# 11-multimodal-combined-sensor.net
KiCad netlist of a schematic drawn in Altium Designer
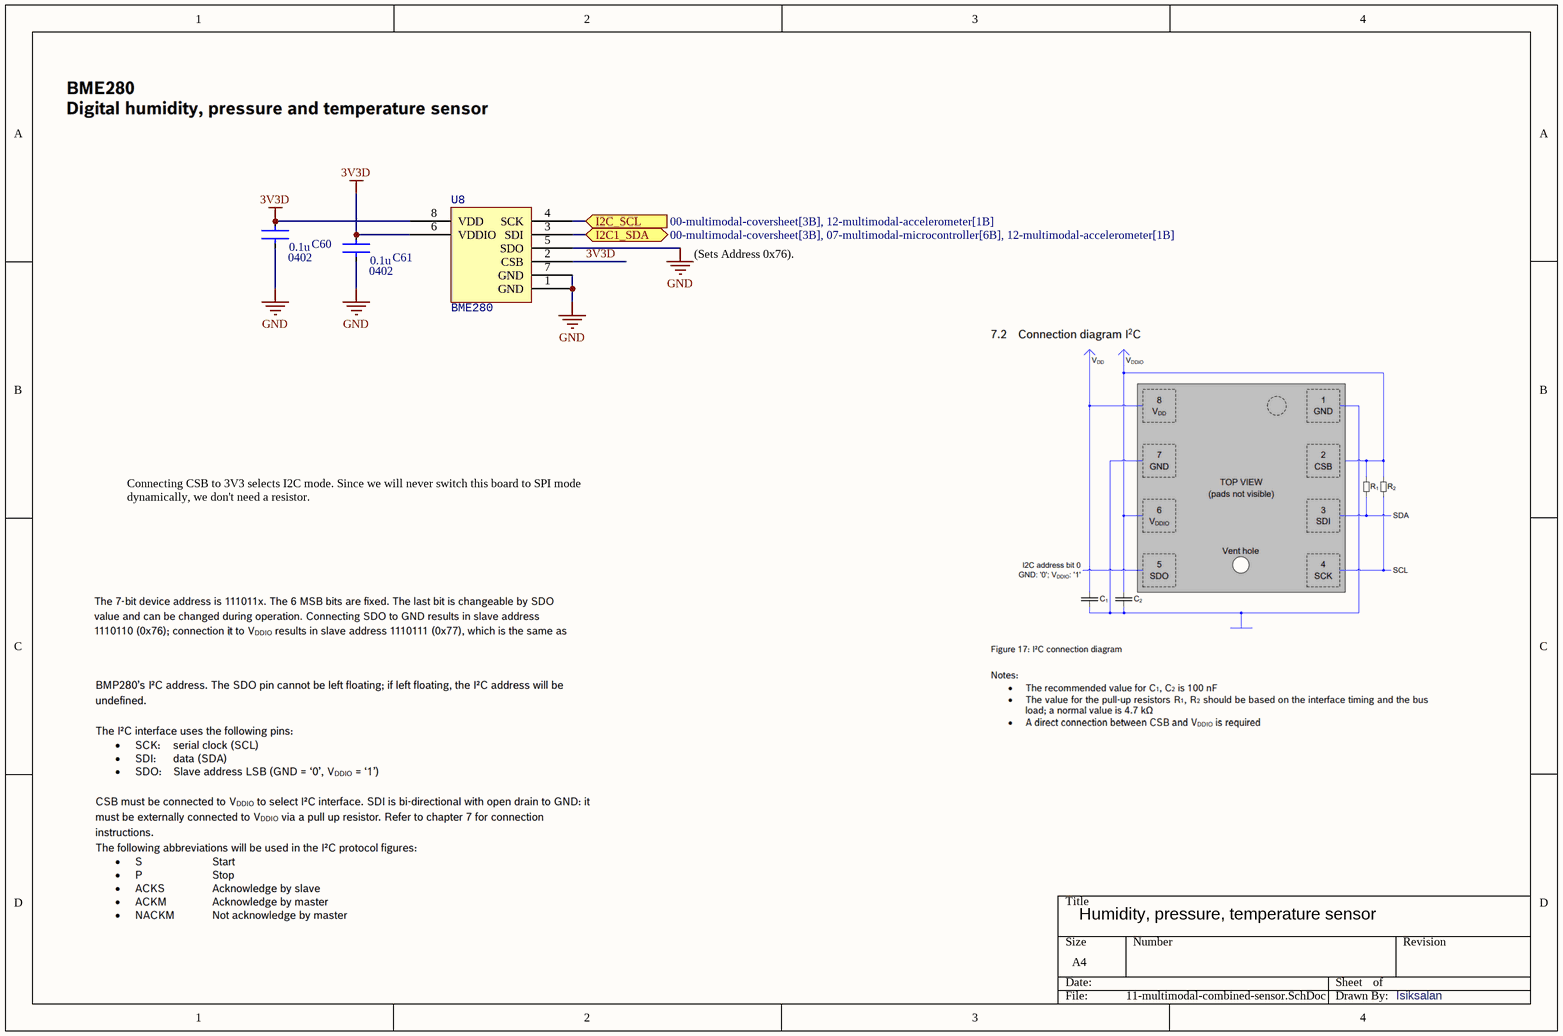
[diagram p0: 11-multimodal-combined-sensor.SchDoc]

(export (version "E")
  (design (tool "Eeschema 10.0.6"))
  (components
    (comp (ref "C60")
      (value "C1005X7R1H104K050BB")
      (footprint "CAPTDK0402")
      (description "CAP CER 0.1UF 50V X7R 0402")
      (libsource (lib "multimodal") (part "C1005X7R1H104K050BB"))
    )
    (comp (ref "C61")
      (value "C1005X7R1H104K050BB")
      (footprint "CAPTDK0402")
      (description "CAP CER 0.1UF 50V X7R 0402")
      (libsource (lib "multimodal") (part "C1005X7R1H104K050BB"))
    )
    (comp (ref "U8")
      (value "BME280")
      (footprint "BME280_FOOTPRINT")
      (libsource (lib "multimodal") (part "BME280"))
    )
  )
  (nets
    (net (code "1") (name "/I2C1_SDA") (class "Default")
      (node (ref "U8") (pin "3") (pinfunction "SDI_3") (pintype "passive"))
    )
    (net (code "2") (name "/I2C_SCL") (class "Default")
      (node (ref "U8") (pin "4") (pinfunction "SCK_4") (pintype "passive"))
    )
    (net (code "3") (name "3V3D") (class "Default")
      (node (ref "C60") (pin "1") (pinfunction "1_1") (pintype "passive"))
      (node (ref "C61") (pin "1") (pinfunction "1_1") (pintype "passive"))
      (node (ref "U8") (pin "2") (pinfunction "CSB_2") (pintype "passive"))
      (node (ref "U8") (pin "6") (pinfunction "VDDIO_6") (pintype "passive"))
      (node (ref "U8") (pin "8") (pinfunction "VDD_8") (pintype "passive"))
    )
    (net (code "4") (name "GND") (class "Default")
      (node (ref "C60") (pin "2") (pinfunction "2_2") (pintype "passive"))
      (node (ref "C61") (pin "2") (pinfunction "2_2") (pintype "passive"))
      (node (ref "U8") (pin "1") (pinfunction "GND_1") (pintype "passive"))
      (node (ref "U8") (pin "5") (pinfunction "SDO_5") (pintype "passive"))
      (node (ref "U8") (pin "7") (pinfunction "GND_7") (pintype "passive"))
    )
  )
)
